# DownstreamChargingPort.net
KiCad netlist of a schematic drawn in Altium Designer
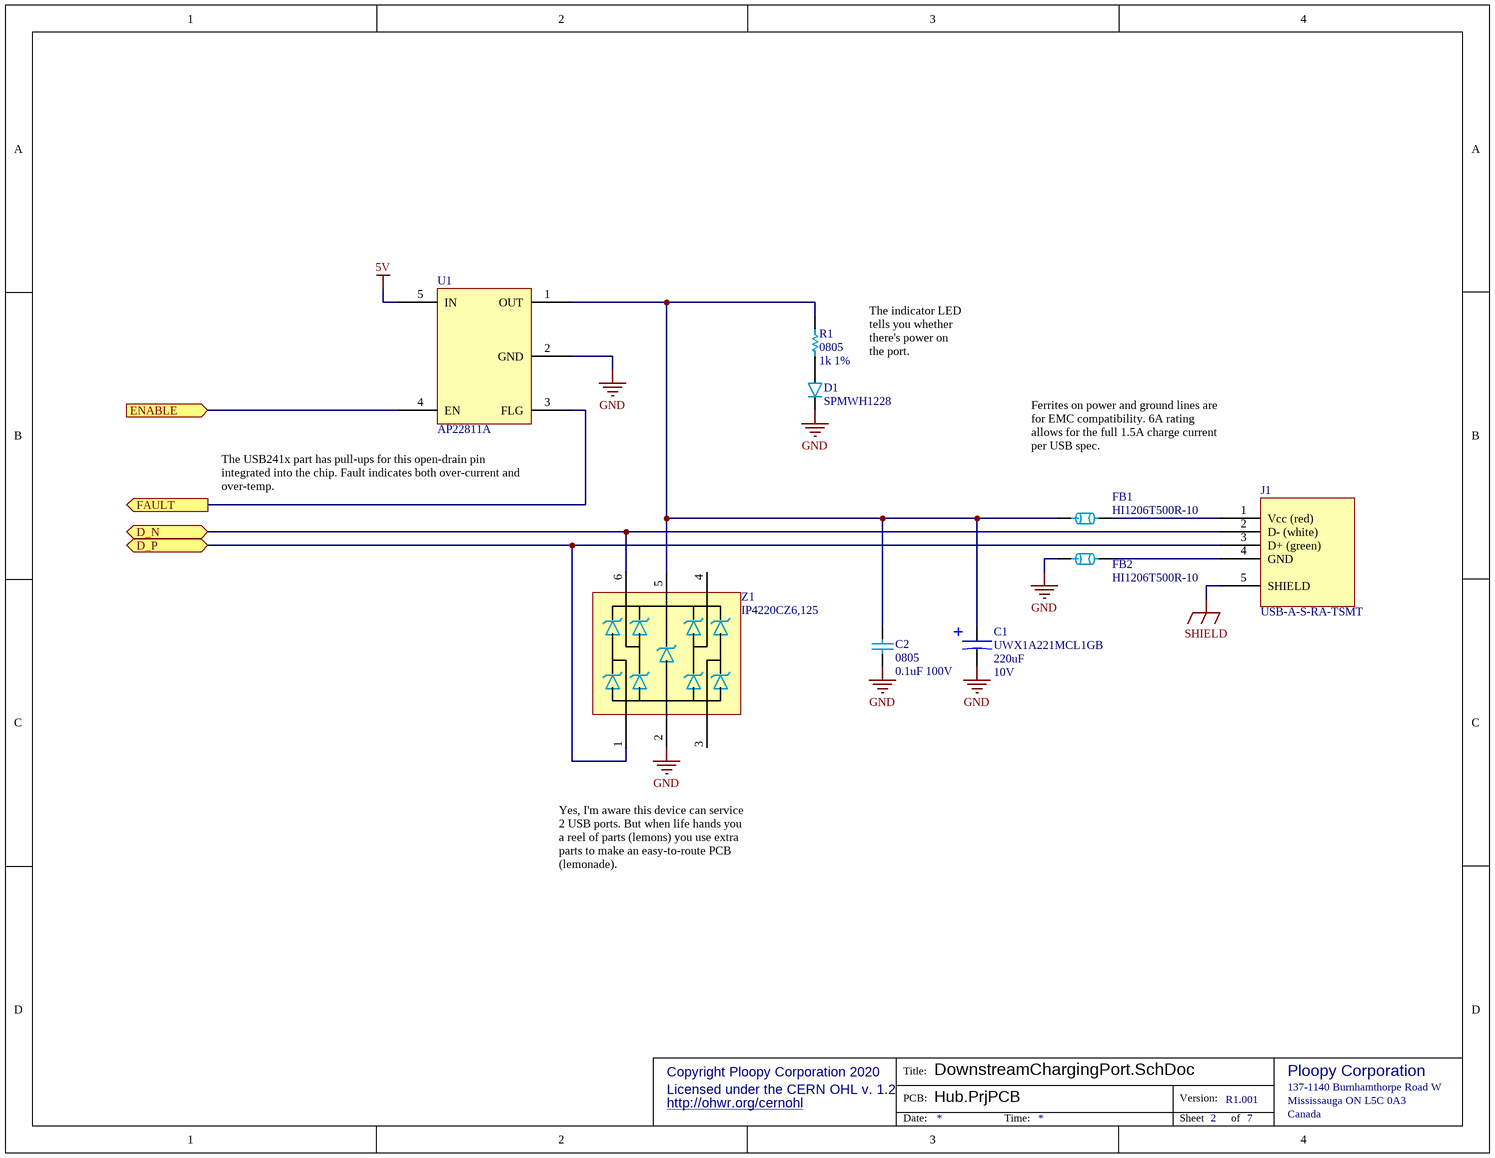
[diagram p0: DownstreamChargingPort.SchDoc]

(export (version "E")
  (design (tool "Eeschema 10.0.6"))
  (components
    (comp (ref "C1")
      (value "UWX1A221MCL1GB")
      (footprint "Nichicon UWX - 8mm x 5.5mm")
      (description "220uF 10V Electrolytic Capacitor, SMD")
      (fields (field (name "ALTIUM_VALUE") "220uF") (field (name "VOLTAGE") "10V"))
      (libsource (lib "Capacitors") (part "UWX1A221MCL1GB"))
    )
    (comp (ref "C2")
      (value "0805")
      (footprint "0805")
      (description "0805, X5R or better")
      (fields (field (name "ALTIUM_VALUE") "0.1uF 100V"))
      (libsource (lib "Chip_Passives") (part "Cap 0.1uF 100V"))
    )
    (comp (ref "D1")
      (value "SPMWH1228")
      (footprint "SPMWH1228")
      (description "3V/0.5W white LED, 2.8mm x 3.5mm")
      (libsource (lib "LEDs") (part "SPMWH1228"))
    )
    (comp (ref "FB1")
      (value "HI1206T500R-10")
      (footprint "1206")
      (description "50 Ohms @ 100MHz 1 Power, Signal Line Ferrite Bead 1206 (3216 Metric) 6A 10mOhm")
      (libsource (lib "Chip_Passives") (part "HI1206T500R-10"))
    )
    (comp (ref "FB2")
      (value "HI1206T500R-10")
      (footprint "1206")
      (description "50 Ohms @ 100MHz 1 Power, Signal Line Ferrite Bead 1206 (3216 Metric) 6A 10mOhm")
      (libsource (lib "Chip_Passives") (part "HI1206T500R-10"))
    )
    (comp (ref "J1")
      (value "USB-A-S-RA-TSMT")
      (footprint "USB-A-S-RA-TSMT")
      (description "USB - A USB 2.0 Receptacle Connector 4 Position Surface Mount, Right Angle")
      (libsource (lib "Connectors") (part "USB-A-S-RA-TSMT"))
    )
    (comp (ref "R1")
      (value "0805")
      (footprint "0805")
      (description "Chip resistor, 1/8W 100PPM")
      (fields (field (name "ALTIUM_VALUE") "1k 1%"))
      (libsource (lib "Chip_Passives") (part "Res 1k 1% 0805"))
    )
    (comp (ref "U1")
      (value "AP22811A")
      (footprint "AP22811 - SOT95P285X140-5M")
      (description "USB Power Switch/Driver 1:1 P-Channel 2A SOT-25")
      (libsource (lib "PowerSupply") (part "AP22811A"))
    )
    (comp (ref "Z1")
      (value "IP4220CZ6,125")
      (footprint "PESD3V3S4UD - SOT95P275X110-6N")
      (description "TVS DIODE 5.5V 6TSOP (Low capacitance, USB)")
      (libsource (lib "Diodes") (part "IP4220CZ6,125"))
    )
  )
  (nets
    (net (code "1") (name "/D_N") (class "Default")
      (node (ref "J1") (pin "2") (pinfunction "D-_(white)_2") (pintype "passive"))
      (node (ref "Z1") (pin "6") (pinfunction "6_6") (pintype "passive"))
    )
    (net (code "2") (name "/D_P") (class "Default")
      (node (ref "J1") (pin "3") (pinfunction "D+_(green)_3") (pintype "passive"))
      (node (ref "Z1") (pin "1") (pinfunction "1_1") (pintype "passive"))
    )
    (net (code "3") (name "/ENABLE") (class "Default")
      (node (ref "U1") (pin "4") (pinfunction "EN_4") (pintype "passive"))
    )
    (net (code "4") (name "/FAULT") (class "Default")
      (node (ref "U1") (pin "3") (pinfunction "FLG_3") (pintype "passive"))
    )
    (net (code "5") (name "5V") (class "Default")
      (node (ref "U1") (pin "5") (pinfunction "IN_5") (pintype "passive"))
    )
    (net (code "6") (name "GND") (class "Default")
      (node (ref "C1") (pin "2") (pinfunction "2_2") (pintype "passive"))
      (node (ref "C2") (pin "1") (pinfunction "1_1") (pintype "passive"))
      (node (ref "D1") (pin "2") (pinfunction "C_2") (pintype "passive"))
      (node (ref "FB2") (pin "1") (pinfunction "1_1") (pintype "passive"))
      (node (ref "U1") (pin "2") (pinfunction "GND_2") (pintype "passive"))
      (node (ref "Z1") (pin "2") (pinfunction "2_2") (pintype "passive"))
    )
    (net (code "7") (name "Net-(D1-A)") (class "Default")
      (node (ref "D1") (pin "1") (pinfunction "A_1") (pintype "passive"))
      (node (ref "R1") (pin "1") (pinfunction "1_1") (pintype "passive"))
    )
    (net (code "8") (name "Net-(J1-GND)") (class "Default")
      (node (ref "FB2") (pin "2") (pinfunction "2_2") (pintype "passive"))
      (node (ref "J1") (pin "4") (pinfunction "GND_4") (pintype "passive"))
    )
    (net (code "9") (name "Net-(J1-Vcc_(red))") (class "Default")
      (node (ref "FB1") (pin "2") (pinfunction "2_2") (pintype "passive"))
      (node (ref "J1") (pin "1") (pinfunction "Vcc_(red)_1") (pintype "passive"))
    )
    (net (code "10") (name "Net-(U1-OUT)") (class "Default")
      (node (ref "C1") (pin "1") (pinfunction "1_1") (pintype "passive"))
      (node (ref "C2") (pin "2") (pinfunction "2_2") (pintype "passive"))
      (node (ref "FB1") (pin "1") (pinfunction "1_1") (pintype "passive"))
      (node (ref "R1") (pin "2") (pinfunction "2_2") (pintype "passive"))
      (node (ref "U1") (pin "1") (pinfunction "OUT_1") (pintype "passive"))
      (node (ref "Z1") (pin "5") (pinfunction "5_5") (pintype "passive"))
    )
    (net (code "11") (name "SHIELD") (class "Default")
      (node (ref "J1") (pin "5") (pinfunction "SHIELD_5") (pintype "passive"))
    )
    (net (code "12") (name "unconnected-(Z1-Pad3)") (class "Default")
      (node (ref "Z1") (pin "3") (pinfunction "3_3") (pintype "passive"))
    )
    (net (code "13") (name "unconnected-(Z1-Pad4)") (class "Default")
      (node (ref "Z1") (pin "4") (pinfunction "4_4") (pintype "passive"))
    )
  )
)
